# SVRBase.net
KiCad netlist of a schematic drawn in EAGLE
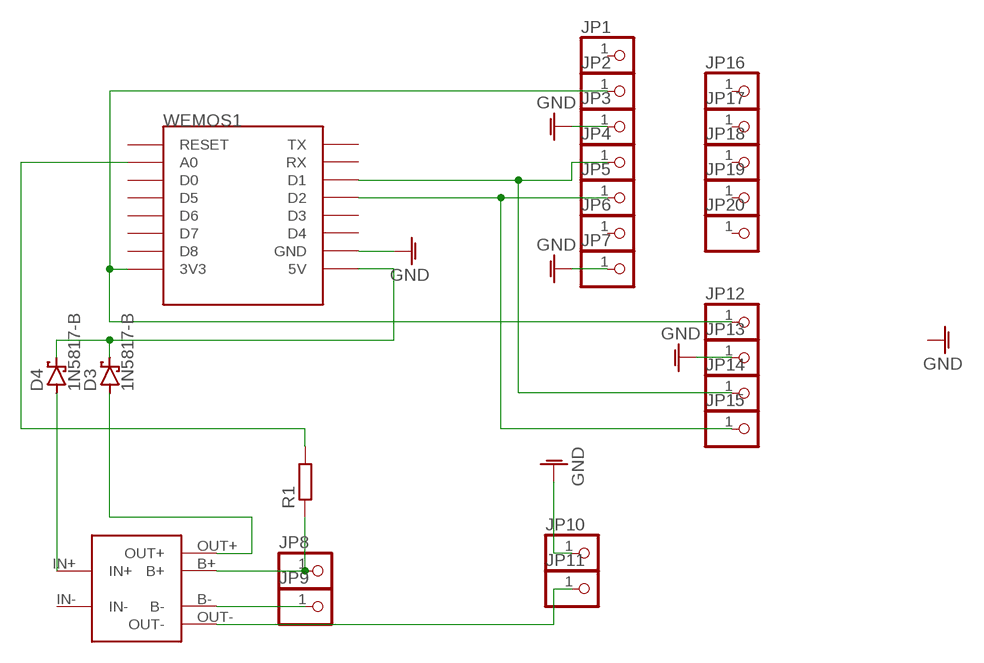
[diagram p0: schematic, sheet 1]

(export (version "E")
  (design (tool "Eeschema 10.0.6"))
  (components
    (comp (ref "CHARGING")
      (value "TP4056-PTH")
      (footprint "eagle-import:TP4056-PTH")
      (libsource (lib "eagle-import") (part "TP4056-PTH"))
    )
    (comp (ref "D3")
      (value "1N5817-B")
      (footprint "eagle-import:DO41-7.6")
      (libsource (lib "eagle-import") (part "1N5817-B"))
    )
    (comp (ref "D4")
      (value "1N5817-B")
      (footprint "eagle-import:DO41-7.6")
      (libsource (lib "eagle-import") (part "1N5817-B"))
    )
    (comp (ref "JP1")
      (value "PINHD-1X1")
      (footprint "eagle-import:1X01")
      (libsource (lib "eagle-import") (part "PINHD-1X1"))
    )
    (comp (ref "JP2")
      (value "PINHD-1X1")
      (footprint "eagle-import:1X01")
      (libsource (lib "eagle-import") (part "PINHD-1X1"))
    )
    (comp (ref "JP3")
      (value "PINHD-1X1")
      (footprint "eagle-import:1X01")
      (libsource (lib "eagle-import") (part "PINHD-1X1"))
    )
    (comp (ref "JP4")
      (value "PINHD-1X1")
      (footprint "eagle-import:1X01")
      (libsource (lib "eagle-import") (part "PINHD-1X1"))
    )
    (comp (ref "JP5")
      (value "PINHD-1X1")
      (footprint "eagle-import:1X01")
      (libsource (lib "eagle-import") (part "PINHD-1X1"))
    )
    (comp (ref "JP6")
      (value "PINHD-1X1")
      (footprint "eagle-import:1X01")
      (libsource (lib "eagle-import") (part "PINHD-1X1"))
    )
    (comp (ref "JP7")
      (value "PINHD-1X1")
      (footprint "eagle-import:1X01")
      (libsource (lib "eagle-import") (part "PINHD-1X1"))
    )
    (comp (ref "JP8")
      (value "PINHD-1X1")
      (footprint "eagle-import:1X01")
      (libsource (lib "eagle-import") (part "PINHD-1X1"))
    )
    (comp (ref "JP9")
      (value "PINHD-1X1")
      (footprint "eagle-import:1X01")
      (libsource (lib "eagle-import") (part "PINHD-1X1"))
    )
    (comp (ref "JP10")
      (value "PINHD-1X1")
      (footprint "eagle-import:1X01")
      (libsource (lib "eagle-import") (part "PINHD-1X1"))
    )
    (comp (ref "JP11")
      (value "PINHD-1X1")
      (footprint "eagle-import:1X01")
      (libsource (lib "eagle-import") (part "PINHD-1X1"))
    )
    (comp (ref "JP12")
      (value "PINHD-1X1")
      (footprint "eagle-import:1X01")
      (libsource (lib "eagle-import") (part "PINHD-1X1"))
    )
    (comp (ref "JP13")
      (value "PINHD-1X1")
      (footprint "eagle-import:1X01")
      (libsource (lib "eagle-import") (part "PINHD-1X1"))
    )
    (comp (ref "JP14")
      (value "PINHD-1X1")
      (footprint "eagle-import:1X01")
      (libsource (lib "eagle-import") (part "PINHD-1X1"))
    )
    (comp (ref "JP15")
      (value "PINHD-1X1")
      (footprint "eagle-import:1X01")
      (libsource (lib "eagle-import") (part "PINHD-1X1"))
    )
    (comp (ref "JP16")
      (value "PINHD-1X1")
      (footprint "eagle-import:1X01")
      (libsource (lib "eagle-import") (part "PINHD-1X1"))
    )
    (comp (ref "JP17")
      (value "PINHD-1X1")
      (footprint "eagle-import:1X01")
      (libsource (lib "eagle-import") (part "PINHD-1X1"))
    )
    (comp (ref "JP18")
      (value "PINHD-1X1")
      (footprint "eagle-import:1X01")
      (libsource (lib "eagle-import") (part "PINHD-1X1"))
    )
    (comp (ref "JP19")
      (value "PINHD-1X1")
      (footprint "eagle-import:1X01")
      (libsource (lib "eagle-import") (part "PINHD-1X1"))
    )
    (comp (ref "JP20")
      (value "PINHD-1X1")
      (footprint "eagle-import:1X01")
      (libsource (lib "eagle-import") (part "PINHD-1X1"))
    )
    (comp (ref "R1")
      (value "R-EU_0204/7")
      (footprint "eagle-import:0204_7")
      (libsource (lib "eagle-import") (part "R-EU_0204/7"))
    )
    (comp (ref "WEMOS1")
      (value "WEMOS-D1-MINI")
      (footprint "eagle-import:WEMOS-D1-MINI")
      (libsource (lib "eagle-import") (part "WEMOS-D1-MINI"))
    )
  )
  (nets
    (net (code "1") (name "GND") (class "Default")
      (node (ref "JP10") (pin "1") (pinfunction "1_1") (pintype "passive"))
      (node (ref "JP13") (pin "1") (pinfunction "1_1") (pintype "passive"))
      (node (ref "JP3") (pin "1") (pinfunction "1_1") (pintype "passive"))
      (node (ref "JP7") (pin "1") (pinfunction "1_1") (pintype "passive"))
      (node (ref "WEMOS1") (pin "GND") (pinfunction "GND_GND") (pintype "bidirectional"))
    )
    (net (code "2") (name "Net-(CHARGING-PadB+)") (class "Default")
      (node (ref "CHARGING") (pin "B+") (pinfunction "B+_B+") (pintype "bidirectional"))
      (node (ref "JP8") (pin "1") (pinfunction "1_1") (pintype "passive"))
      (node (ref "R1") (pin "1") (pinfunction "1_1") (pintype "passive"))
    )
    (net (code "3") (name "Net-(CHARGING-PadB-)") (class "Default")
      (node (ref "CHARGING") (pin "B-") (pinfunction "B-_B-") (pintype "bidirectional"))
      (node (ref "JP9") (pin "1") (pinfunction "1_1") (pintype "passive"))
    )
    (net (code "4") (name "Net-(CHARGING-PadIN+)") (class "Default")
      (node (ref "CHARGING") (pin "IN+") (pinfunction "IN+_IN+") (pintype "bidirectional"))
      (node (ref "D4") (pin "A") (pinfunction "A_A") (pintype "passive"))
    )
    (net (code "5") (name "Net-(CHARGING-PadOUT+)") (class "Default")
      (node (ref "CHARGING") (pin "OUT+") (pinfunction "OUT+_OUT+") (pintype "bidirectional"))
      (node (ref "D3") (pin "A") (pinfunction "A_A") (pintype "passive"))
    )
    (net (code "6") (name "Net-(CHARGING-PadOUT-)") (class "Default")
      (node (ref "CHARGING") (pin "OUT-") (pinfunction "OUT-_OUT-") (pintype "bidirectional"))
      (node (ref "JP11") (pin "1") (pinfunction "1_1") (pintype "passive"))
    )
    (net (code "7") (name "Net-(D3-PadC)") (class "Default")
      (node (ref "D3") (pin "C") (pinfunction "C_C") (pintype "passive"))
      (node (ref "D4") (pin "C") (pinfunction "C_C") (pintype "passive"))
      (node (ref "WEMOS1") (pin "5V") (pinfunction "5V_5V") (pintype "bidirectional"))
    )
    (net (code "8") (name "Net-(JP12-Pad1)") (class "Default")
      (node (ref "JP12") (pin "1") (pinfunction "1_1") (pintype "passive"))
      (node (ref "JP2") (pin "1") (pinfunction "1_1") (pintype "passive"))
      (node (ref "WEMOS1") (pin "3V3") (pinfunction "3V3_3V3") (pintype "bidirectional"))
    )
    (net (code "9") (name "Net-(JP14-Pad1)") (class "Default")
      (node (ref "JP14") (pin "1") (pinfunction "1_1") (pintype "passive"))
      (node (ref "JP4") (pin "1") (pinfunction "1_1") (pintype "passive"))
      (node (ref "WEMOS1") (pin "D1") (pinfunction "D1_D1") (pintype "bidirectional"))
    )
    (net (code "10") (name "Net-(JP15-Pad1)") (class "Default")
      (node (ref "JP15") (pin "1") (pinfunction "1_1") (pintype "passive"))
      (node (ref "JP5") (pin "1") (pinfunction "1_1") (pintype "passive"))
      (node (ref "WEMOS1") (pin "D2") (pinfunction "D2_D2") (pintype "bidirectional"))
    )
    (net (code "11") (name "Net-(R1-Pad2)") (class "Default")
      (node (ref "R1") (pin "2") (pinfunction "2_2") (pintype "passive"))
      (node (ref "WEMOS1") (pin "A0") (pinfunction "A0_A0") (pintype "bidirectional"))
    )
    (net (code "12") (name "unconnected-(CHARGING-PadIN-)") (class "Default")
      (node (ref "CHARGING") (pin "IN-") (pinfunction "IN-_IN-") (pintype "bidirectional"))
    )
    (net (code "13") (name "unconnected-(JP1-Pad1)") (class "Default")
      (node (ref "JP1") (pin "1") (pinfunction "1_1") (pintype "passive"))
    )
    (net (code "14") (name "unconnected-(JP6-Pad1)") (class "Default")
      (node (ref "JP6") (pin "1") (pinfunction "1_1") (pintype "passive"))
    )
    (net (code "15") (name "unconnected-(JP16-Pad1)") (class "Default")
      (node (ref "JP16") (pin "1") (pinfunction "1_1") (pintype "passive"))
    )
    (net (code "16") (name "unconnected-(JP17-Pad1)") (class "Default")
      (node (ref "JP17") (pin "1") (pinfunction "1_1") (pintype "passive"))
    )
    (net (code "17") (name "unconnected-(JP18-Pad1)") (class "Default")
      (node (ref "JP18") (pin "1") (pinfunction "1_1") (pintype "passive"))
    )
    (net (code "18") (name "unconnected-(JP19-Pad1)") (class "Default")
      (node (ref "JP19") (pin "1") (pinfunction "1_1") (pintype "passive"))
    )
    (net (code "19") (name "unconnected-(JP20-Pad1)") (class "Default")
      (node (ref "JP20") (pin "1") (pinfunction "1_1") (pintype "passive"))
    )
    (net (code "20") (name "unconnected-(WEMOS1-PadD0)") (class "Default")
      (node (ref "WEMOS1") (pin "D0") (pinfunction "D0_D0") (pintype "bidirectional"))
    )
    (net (code "21") (name "unconnected-(WEMOS1-PadD3)") (class "Default")
      (node (ref "WEMOS1") (pin "D3") (pinfunction "D3_D3") (pintype "bidirectional"))
    )
    (net (code "22") (name "unconnected-(WEMOS1-PadD4)") (class "Default")
      (node (ref "WEMOS1") (pin "D4") (pinfunction "D4_D4") (pintype "bidirectional"))
    )
    (net (code "23") (name "unconnected-(WEMOS1-PadD5)") (class "Default")
      (node (ref "WEMOS1") (pin "D5") (pinfunction "D5_D5") (pintype "bidirectional"))
    )
    (net (code "24") (name "unconnected-(WEMOS1-PadD6)") (class "Default")
      (node (ref "WEMOS1") (pin "D6") (pinfunction "D6_D6") (pintype "bidirectional"))
    )
    (net (code "25") (name "unconnected-(WEMOS1-PadD7)") (class "Default")
      (node (ref "WEMOS1") (pin "D7") (pinfunction "D7_D7") (pintype "bidirectional"))
    )
    (net (code "26") (name "unconnected-(WEMOS1-PadD8)") (class "Default")
      (node (ref "WEMOS1") (pin "D8") (pinfunction "D8_D8") (pintype "bidirectional"))
    )
    (net (code "27") (name "unconnected-(WEMOS1-PadRESET)") (class "Default")
      (node (ref "WEMOS1") (pin "RESET") (pinfunction "RESET_RESET") (pintype "bidirectional"))
    )
    (net (code "28") (name "unconnected-(WEMOS1-PadRX)") (class "Default")
      (node (ref "WEMOS1") (pin "RX") (pinfunction "RX_RX") (pintype "bidirectional"))
    )
    (net (code "29") (name "unconnected-(WEMOS1-PadTX)") (class "Default")
      (node (ref "WEMOS1") (pin "TX") (pinfunction "TX_TX") (pintype "bidirectional"))
    )
  )
)
